# Sheet1.net
KiCad netlist of a schematic drawn in Altium Designer
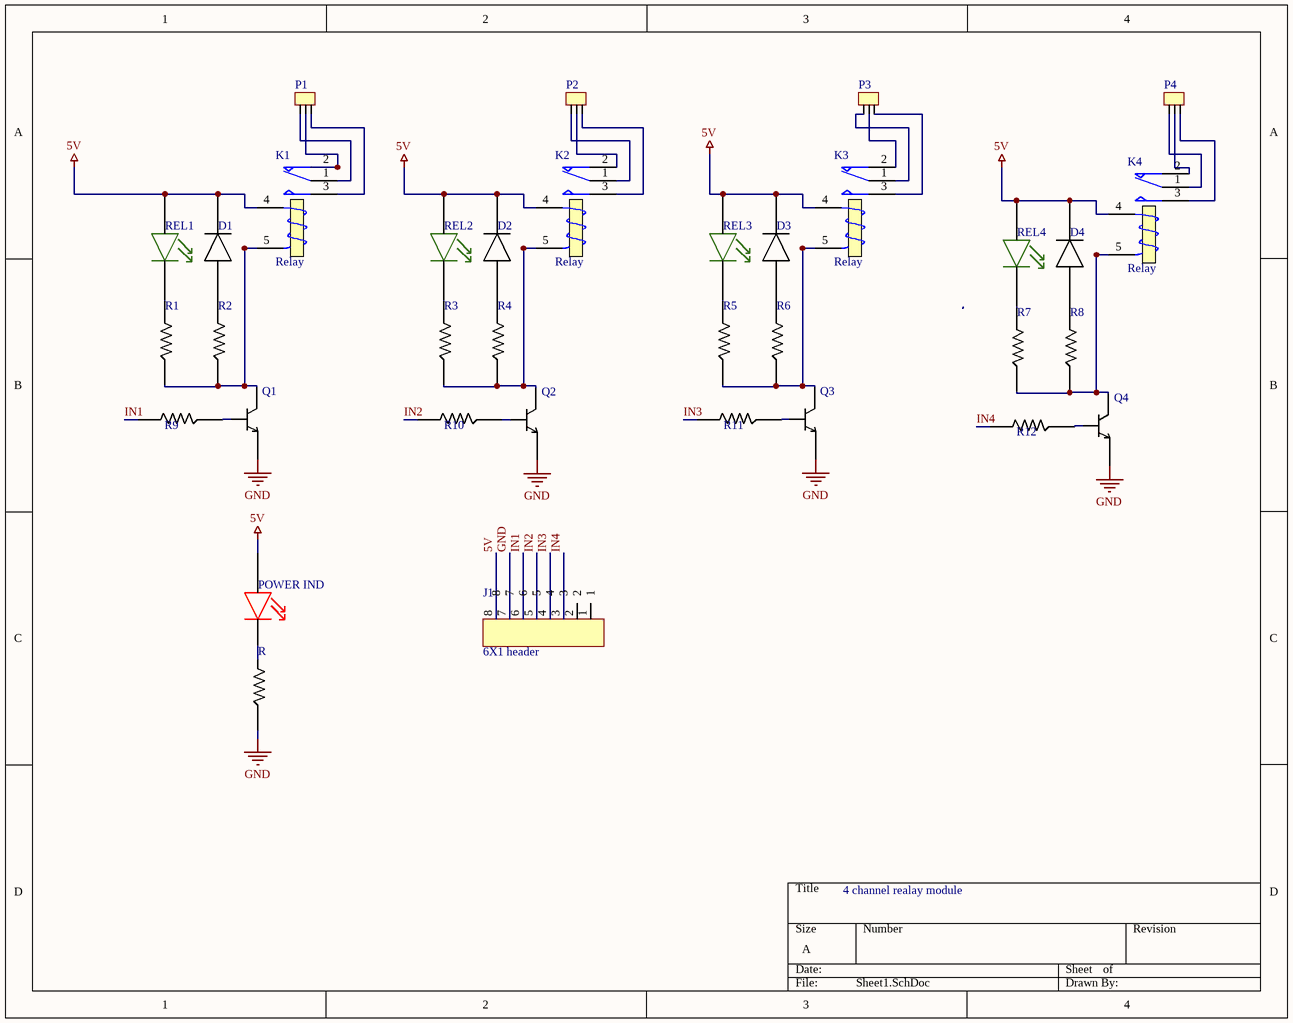
[diagram p0: Sheet1.SchDoc]

(export (version "E")
  (design (tool "Eeschema 10.0.6"))
  (components
    (comp (ref "D1") (value "Diode") (footprint "Diode-1N4007") (libsource (lib "Schlib1") (part "Diode")))
    (comp (ref "D2") (value "Diode") (footprint "Diode-1N4007") (libsource (lib "Schlib1") (part "Diode")))
    (comp (ref "D3") (value "Diode") (footprint "Diode-1N4007") (libsource (lib "Schlib1") (part "Diode")))
    (comp (ref "D4") (value "Diode") (footprint "Diode-1N4007") (libsource (lib "Schlib1") (part "Diode")))
    (comp (ref "J1")
      (value "6X1 header")
      (footprint "6X1 pin header - duplicate")
      (libsource (lib "Schlib1") (part "6X1 header"))
    )
    (comp (ref "K1")
      (value "Relay")
      (footprint "MODULE5B")
      (description "SPDT Relay")
      (fields (field (name "PUBLISHER") "Altium Limited"))
      (libsource (lib "Miscellaneous Devices") (part "Relay"))
    )
    (comp (ref "K2")
      (value "Relay")
      (footprint "MODULE5B")
      (description "SPDT Relay")
      (fields (field (name "PUBLISHER") "Altium Limited"))
      (libsource (lib "Miscellaneous Devices") (part "Relay"))
    )
    (comp (ref "K3")
      (value "Relay")
      (footprint "MODULE5B")
      (description "SPDT Relay")
      (fields (field (name "PUBLISHER") "Altium Limited"))
      (libsource (lib "Miscellaneous Devices") (part "Relay"))
    )
    (comp (ref "K4")
      (value "Relay")
      (footprint "MODULE5B")
      (description "SPDT Relay")
      (fields (field (name "PUBLISHER") "Altium Limited"))
      (libsource (lib "Miscellaneous Devices") (part "Relay"))
    )
    (comp (ref "P1")
      (value "through hole screw terminal")
      (footprint "3X1 screw terminal")
      (libsource (lib "Schlib1") (part "through hole screw terminal"))
    )
    (comp (ref "P2")
      (value "through hole screw terminal")
      (footprint "3X1 screw terminal")
      (libsource (lib "Schlib1") (part "through hole screw terminal"))
    )
    (comp (ref "P3")
      (value "through hole screw terminal")
      (footprint "3X1 screw terminal")
      (libsource (lib "Schlib1") (part "through hole screw terminal"))
    )
    (comp (ref "P4")
      (value "through hole screw terminal")
      (footprint "3X1 screw terminal")
      (libsource (lib "Schlib1") (part "through hole screw terminal"))
    )
    (comp (ref "POWER IND")
      (value "LED_RED_SMD")
      (footprint "LSM0805 Series green")
      (libsource (lib "Schlib1") (part "LED_RED_SMD"))
    )
    (comp (ref "Q1")
      (value "Q1")
      (footprint "transistor BC547 RCC1206 e3")
      (libsource (lib "Schlib1") (part "BC547_SMD"))
    )
    (comp (ref "Q2")
      (value "Q2")
      (footprint "transistor BC547 RCC1206 e3")
      (libsource (lib "Schlib1") (part "BC547_SMD"))
    )
    (comp (ref "Q3")
      (value "Q1")
      (footprint "transistor BC547 RCC1206 e3")
      (libsource (lib "Schlib1") (part "BC547_SMD"))
    )
    (comp (ref "Q4")
      (value "Q1")
      (footprint "transistor BC547 RCC1206 e3")
      (libsource (lib "Schlib1") (part "BC547_SMD"))
    )
    (comp (ref "R")
      (value "resistor")
      (footprint "Resistor-RCC1206 e3")
      (libsource (lib "Schlib1") (part "resistor"))
    )
    (comp (ref "R1")
      (value "resistor")
      (footprint "Resistor-RCC1206 e3")
      (libsource (lib "Schlib1") (part "resistor"))
    )
    (comp (ref "R2")
      (value "resistor")
      (footprint "Resistor-RCC1206 e3")
      (libsource (lib "Schlib1") (part "resistor"))
    )
    (comp (ref "R3")
      (value "resistor")
      (footprint "Resistor-RCC1206 e3")
      (libsource (lib "Schlib1") (part "resistor"))
    )
    (comp (ref "R4")
      (value "resistor")
      (footprint "Resistor-RCC1206 e3")
      (libsource (lib "Schlib1") (part "resistor"))
    )
    (comp (ref "R5")
      (value "resistor")
      (footprint "Resistor-RCC1206 e3")
      (libsource (lib "Schlib1") (part "resistor"))
    )
    (comp (ref "R6")
      (value "resistor")
      (footprint "Resistor-RCC1206 e3")
      (libsource (lib "Schlib1") (part "resistor"))
    )
    (comp (ref "R7")
      (value "resistor")
      (footprint "Resistor-RCC1206 e3")
      (libsource (lib "Schlib1") (part "resistor"))
    )
    (comp (ref "R8")
      (value "resistor")
      (footprint "Resistor-RCC1206 e3")
      (libsource (lib "Schlib1") (part "resistor"))
    )
    (comp (ref "R9")
      (value "resistor")
      (footprint "Resistor-RCC1206 e3")
      (libsource (lib "Schlib1") (part "resistor"))
    )
    (comp (ref "R10")
      (value "resistor")
      (footprint "Resistor-RCC1206 e3")
      (libsource (lib "Schlib1") (part "resistor"))
    )
    (comp (ref "R11")
      (value "resistor")
      (footprint "Resistor-RCC1206 e3")
      (libsource (lib "Schlib1") (part "resistor"))
    )
    (comp (ref "R12")
      (value "resistor")
      (footprint "Resistor-RCC1206 e3")
      (libsource (lib "Schlib1") (part "resistor"))
    )
    (comp (ref "REL1")
      (value "LED_GREEN_SMD")
      (footprint "LSM0805452V-Green")
      (libsource (lib "Schlib1") (part "LED_GREEN_SMD"))
    )
    (comp (ref "REL2")
      (value "LED_GREEN_SMD")
      (footprint "LSM0805452V-Green")
      (libsource (lib "Schlib1") (part "LED_GREEN_SMD"))
    )
    (comp (ref "REL3")
      (value "LED_GREEN_SMD")
      (footprint "LSM0805452V-Green")
      (libsource (lib "Schlib1") (part "LED_GREEN_SMD"))
    )
    (comp (ref "REL4")
      (value "LED_GREEN_SMD")
      (footprint "LSM0805452V-Green")
      (libsource (lib "Schlib1") (part "LED_GREEN_SMD"))
    )
  )
  (nets
    (net (code "1") (name "/IN1") (class "Default")
      (node (ref "J1") (pin "6") (pinfunction "6_6") (pintype "passive"))
      (node (ref "R9") (pin "1") (pinfunction "1_1") (pintype "passive"))
    )
    (net (code "2") (name "/IN2") (class "Default")
      (node (ref "J1") (pin "5") (pinfunction "5_5") (pintype "passive"))
      (node (ref "R10") (pin "1") (pinfunction "1_1") (pintype "passive"))
    )
    (net (code "3") (name "/IN3") (class "Default")
      (node (ref "J1") (pin "4") (pinfunction "4_4") (pintype "passive"))
      (node (ref "R11") (pin "1") (pinfunction "1_1") (pintype "passive"))
    )
    (net (code "4") (name "/IN4") (class "Default")
      (node (ref "J1") (pin "3") (pinfunction "3_3") (pintype "passive"))
      (node (ref "R12") (pin "1") (pinfunction "1_1") (pintype "passive"))
    )
    (net (code "5") (name "5V") (class "Default")
      (node (ref "D1") (pin "K") (pinfunction "K_K") (pintype "passive"))
      (node (ref "D2") (pin "K") (pinfunction "K_K") (pintype "passive"))
      (node (ref "D3") (pin "K") (pinfunction "K_K") (pintype "passive"))
      (node (ref "D4") (pin "K") (pinfunction "K_K") (pintype "passive"))
      (node (ref "J1") (pin "8") (pinfunction "8_8") (pintype "passive"))
      (node (ref "K1") (pin "4") (pinfunction "T1_4") (pintype "passive"))
      (node (ref "K2") (pin "4") (pinfunction "T1_4") (pintype "passive"))
      (node (ref "K3") (pin "4") (pinfunction "T1_4") (pintype "passive"))
      (node (ref "K4") (pin "4") (pinfunction "T1_4") (pintype "passive"))
      (node (ref "POWER IND") (pin "A") (pinfunction "A_A") (pintype "passive"))
      (node (ref "REL1") (pin "A") (pinfunction "A_A") (pintype "passive"))
      (node (ref "REL2") (pin "A") (pinfunction "A_A") (pintype "passive"))
      (node (ref "REL3") (pin "A") (pinfunction "A_A") (pintype "passive"))
      (node (ref "REL4") (pin "A") (pinfunction "A_A") (pintype "passive"))
    )
    (net (code "6") (name "GND") (class "Default")
      (node (ref "J1") (pin "7") (pinfunction "7_7") (pintype "passive"))
      (node (ref "Q1") (pin "3") (pinfunction "E_3") (pintype "passive"))
      (node (ref "Q2") (pin "3") (pinfunction "E_3") (pintype "passive"))
      (node (ref "Q3") (pin "3") (pinfunction "E_3") (pintype "passive"))
      (node (ref "Q4") (pin "3") (pinfunction "E_3") (pintype "passive"))
      (node (ref "R") (pin "2") (pinfunction "2_2") (pintype "passive"))
    )
    (net (code "7") (name "Net-(D1-PadA)") (class "Default")
      (node (ref "D1") (pin "A") (pinfunction "A_A") (pintype "passive"))
      (node (ref "R2") (pin "1") (pinfunction "1_1") (pintype "passive"))
    )
    (net (code "8") (name "Net-(D2-PadA)") (class "Default")
      (node (ref "D2") (pin "A") (pinfunction "A_A") (pintype "passive"))
      (node (ref "R4") (pin "1") (pinfunction "1_1") (pintype "passive"))
    )
    (net (code "9") (name "Net-(D3-PadA)") (class "Default")
      (node (ref "D3") (pin "A") (pinfunction "A_A") (pintype "passive"))
      (node (ref "R6") (pin "1") (pinfunction "1_1") (pintype "passive"))
    )
    (net (code "10") (name "Net-(D4-PadA)") (class "Default")
      (node (ref "D4") (pin "A") (pinfunction "A_A") (pintype "passive"))
      (node (ref "R8") (pin "1") (pinfunction "1_1") (pintype "passive"))
    )
    (net (code "11") (name "Net-(K1-COM)") (class "Default")
      (node (ref "K1") (pin "1") (pinfunction "COM_1") (pintype "passive"))
      (node (ref "P1") (pin "1") (pinfunction "1_1") (pintype "passive"))
    )
    (net (code "12") (name "Net-(K1-NC)") (class "Default")
      (node (ref "K1") (pin "2") (pinfunction "NC_2") (pintype "passive"))
      (node (ref "P1") (pin "2") (pinfunction "2_2") (pintype "passive"))
    )
    (net (code "13") (name "Net-(K1-NO)") (class "Default")
      (node (ref "K1") (pin "3") (pinfunction "NO_3") (pintype "passive"))
      (node (ref "P1") (pin "3") (pinfunction "3_3") (pintype "passive"))
    )
    (net (code "14") (name "Net-(K1-T2)") (class "Default")
      (node (ref "K1") (pin "5") (pinfunction "T2_5") (pintype "passive"))
      (node (ref "Q1") (pin "1") (pinfunction "C_1") (pintype "passive"))
      (node (ref "R1") (pin "2") (pinfunction "2_2") (pintype "passive"))
      (node (ref "R2") (pin "2") (pinfunction "2_2") (pintype "passive"))
    )
    (net (code "15") (name "Net-(K2-COM)") (class "Default")
      (node (ref "K2") (pin "1") (pinfunction "COM_1") (pintype "passive"))
      (node (ref "P2") (pin "1") (pinfunction "1_1") (pintype "passive"))
    )
    (net (code "16") (name "Net-(K2-NC)") (class "Default")
      (node (ref "K2") (pin "2") (pinfunction "NC_2") (pintype "passive"))
      (node (ref "P2") (pin "2") (pinfunction "2_2") (pintype "passive"))
    )
    (net (code "17") (name "Net-(K2-NO)") (class "Default")
      (node (ref "K2") (pin "3") (pinfunction "NO_3") (pintype "passive"))
      (node (ref "P2") (pin "3") (pinfunction "3_3") (pintype "passive"))
    )
    (net (code "18") (name "Net-(K2-T2)") (class "Default")
      (node (ref "K2") (pin "5") (pinfunction "T2_5") (pintype "passive"))
      (node (ref "Q2") (pin "1") (pinfunction "C_1") (pintype "passive"))
      (node (ref "R3") (pin "2") (pinfunction "2_2") (pintype "passive"))
      (node (ref "R4") (pin "2") (pinfunction "2_2") (pintype "passive"))
    )
    (net (code "19") (name "Net-(K3-COM)") (class "Default")
      (node (ref "K3") (pin "1") (pinfunction "COM_1") (pintype "passive"))
      (node (ref "P3") (pin "1") (pinfunction "1_1") (pintype "passive"))
    )
    (net (code "20") (name "Net-(K3-NC)") (class "Default")
      (node (ref "K3") (pin "2") (pinfunction "NC_2") (pintype "passive"))
      (node (ref "P3") (pin "2") (pinfunction "2_2") (pintype "passive"))
    )
    (net (code "21") (name "Net-(K3-NO)") (class "Default")
      (node (ref "K3") (pin "3") (pinfunction "NO_3") (pintype "passive"))
      (node (ref "P3") (pin "3") (pinfunction "3_3") (pintype "passive"))
    )
    (net (code "22") (name "Net-(K3-T2)") (class "Default")
      (node (ref "K3") (pin "5") (pinfunction "T2_5") (pintype "passive"))
      (node (ref "Q3") (pin "1") (pinfunction "C_1") (pintype "passive"))
      (node (ref "R5") (pin "2") (pinfunction "2_2") (pintype "passive"))
      (node (ref "R6") (pin "2") (pinfunction "2_2") (pintype "passive"))
    )
    (net (code "23") (name "Net-(K4-COM)") (class "Default")
      (node (ref "K4") (pin "1") (pinfunction "COM_1") (pintype "passive"))
      (node (ref "P4") (pin "1") (pinfunction "1_1") (pintype "passive"))
    )
    (net (code "24") (name "Net-(K4-NC)") (class "Default")
      (node (ref "K4") (pin "2") (pinfunction "NC_2") (pintype "passive"))
      (node (ref "P4") (pin "2") (pinfunction "2_2") (pintype "passive"))
    )
    (net (code "25") (name "Net-(K4-NO)") (class "Default")
      (node (ref "K4") (pin "3") (pinfunction "NO_3") (pintype "passive"))
      (node (ref "P4") (pin "3") (pinfunction "3_3") (pintype "passive"))
    )
    (net (code "26") (name "Net-(K4-T2)") (class "Default")
      (node (ref "K4") (pin "5") (pinfunction "T2_5") (pintype "passive"))
      (node (ref "Q4") (pin "1") (pinfunction "C_1") (pintype "passive"))
      (node (ref "R7") (pin "2") (pinfunction "2_2") (pintype "passive"))
      (node (ref "R8") (pin "2") (pinfunction "2_2") (pintype "passive"))
    )
    (net (code "27") (name "Net-(POWER IND-PadK)") (class "Default")
      (node (ref "POWER IND") (pin "K") (pinfunction "K_K") (pintype "passive"))
      (node (ref "R") (pin "1") (pinfunction "1_1") (pintype "passive"))
    )
    (net (code "28") (name "Net-(Q1-B)") (class "Default")
      (node (ref "Q1") (pin "2") (pinfunction "B_2") (pintype "passive"))
      (node (ref "R9") (pin "2") (pinfunction "2_2") (pintype "passive"))
    )
    (net (code "29") (name "Net-(Q2-B)") (class "Default")
      (node (ref "Q2") (pin "2") (pinfunction "B_2") (pintype "passive"))
      (node (ref "R10") (pin "2") (pinfunction "2_2") (pintype "passive"))
    )
    (net (code "30") (name "Net-(Q3-B)") (class "Default")
      (node (ref "Q3") (pin "2") (pinfunction "B_2") (pintype "passive"))
      (node (ref "R11") (pin "2") (pinfunction "2_2") (pintype "passive"))
    )
    (net (code "31") (name "Net-(Q4-B)") (class "Default")
      (node (ref "Q4") (pin "2") (pinfunction "B_2") (pintype "passive"))
      (node (ref "R12") (pin "2") (pinfunction "2_2") (pintype "passive"))
    )
    (net (code "32") (name "Net-(R1-Pad1)") (class "Default")
      (node (ref "R1") (pin "1") (pinfunction "1_1") (pintype "passive"))
      (node (ref "REL1") (pin "K") (pinfunction "K_K") (pintype "passive"))
    )
    (net (code "33") (name "Net-(R3-Pad1)") (class "Default")
      (node (ref "R3") (pin "1") (pinfunction "1_1") (pintype "passive"))
      (node (ref "REL2") (pin "K") (pinfunction "K_K") (pintype "passive"))
    )
    (net (code "34") (name "Net-(R5-Pad1)") (class "Default")
      (node (ref "R5") (pin "1") (pinfunction "1_1") (pintype "passive"))
      (node (ref "REL3") (pin "K") (pinfunction "K_K") (pintype "passive"))
    )
    (net (code "35") (name "Net-(R7-Pad1)") (class "Default")
      (node (ref "R7") (pin "1") (pinfunction "1_1") (pintype "passive"))
      (node (ref "REL4") (pin "K") (pinfunction "K_K") (pintype "passive"))
    )
    (net (code "36") (name "unconnected-(J1-Pad1)") (class "Default")
      (node (ref "J1") (pin "1") (pinfunction "1_1") (pintype "passive"))
    )
    (net (code "37") (name "unconnected-(J1-Pad2)") (class "Default")
      (node (ref "J1") (pin "2") (pinfunction "2_2") (pintype "passive"))
    )
  )
)
